# LED_7_Seg.net
KiCad netlist of a schematic drawn in Altium Designer
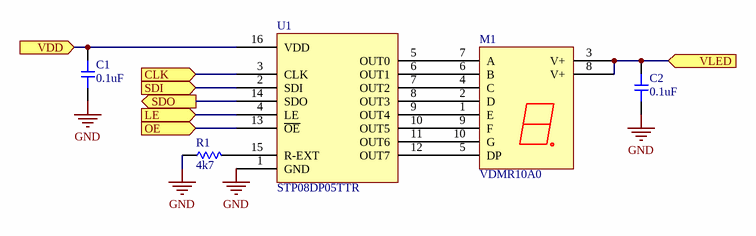
[diagram p0: LED_7_Seg.SchDoc]

(export (version "E")
  (design (tool "Eeschema 10.0.6"))
  (components
    (comp (ref "C1")
      (value "0.1uF")
      (footprint "PcbLib:0603-CAP")
      (description "Capacitor")
      (libsource (lib "AMDC") (part "Capacitor"))
    )
    (comp (ref "C2")
      (value "0.1uF")
      (footprint "PcbLib:0603-CAP")
      (description "Capacitor")
      (libsource (lib "AMDC") (part "Capacitor"))
    )
    (comp (ref "M1")
      (value "VDMR10A0")
      (footprint "VDMR10A0")
      (description "DISPLAY 7SEG 0.39\" SGL RED 10SMD")
      (libsource (lib "Schlib") (part "VDMR10A0"))
    )
    (comp (ref "R1")
      (value "4k7")
      (footprint "PcbLib:0603-RES")
      (fields (field (name "Comment") "Resistor"))
      (libsource (lib "*") (part "Resistor"))
    )
    (comp (ref "U1")
      (value "STP08DP05TTR")
      (footprint "TSOP65P640X120-16N")
      (description "IC LED DRIVER LIN 100MA 16TSSOP")
      (libsource (lib "Schlib") (part "STP08DP05TTR"))
    )
  )
  (nets
    (net (code "1") (name "/CLK") (class "Default")
      (node (ref "U1") (pin "3") (pinfunction "CLK_3") (pintype "passive"))
    )
    (net (code "2") (name "/LE") (class "Default")
      (node (ref "U1") (pin "4") (pinfunction "LE_4") (pintype "passive"))
    )
    (net (code "3") (name "/OE") (class "Default")
      (node (ref "U1") (pin "13") (pinfunction "~{OE}_13") (pintype "passive"))
    )
    (net (code "4") (name "/SDI") (class "Default")
      (node (ref "U1") (pin "2") (pinfunction "SDI_2") (pintype "passive"))
    )
    (net (code "5") (name "/SDO") (class "Default")
      (node (ref "U1") (pin "14") (pinfunction "SDO_14") (pintype "passive"))
    )
    (net (code "6") (name "/VDD") (class "Default")
      (node (ref "C1") (pin "1") (pinfunction "1_1") (pintype "passive"))
      (node (ref "U1") (pin "16") (pinfunction "VDD_16") (pintype "passive"))
    )
    (net (code "7") (name "/VLED") (class "Default")
      (node (ref "C2") (pin "1") (pinfunction "1_1") (pintype "passive"))
      (node (ref "M1") (pin "3") (pinfunction "V+_3") (pintype "passive"))
      (node (ref "M1") (pin "8") (pinfunction "V+_8") (pintype "passive"))
    )
    (net (code "8") (name "GND") (class "Default")
      (node (ref "C1") (pin "2") (pinfunction "2_2") (pintype "passive"))
      (node (ref "C2") (pin "2") (pinfunction "2_2") (pintype "passive"))
      (node (ref "R1") (pin "1") (pinfunction "1_1") (pintype "passive"))
      (node (ref "U1") (pin "1") (pinfunction "GND_1") (pintype "passive"))
    )
    (net (code "9") (name "Net-(M1-A)") (class "Default")
      (node (ref "M1") (pin "7") (pinfunction "A_7") (pintype "passive"))
      (node (ref "U1") (pin "5") (pinfunction "OUT0_5") (pintype "passive"))
    )
    (net (code "10") (name "Net-(M1-B)") (class "Default")
      (node (ref "M1") (pin "6") (pinfunction "B_6") (pintype "passive"))
      (node (ref "U1") (pin "6") (pinfunction "OUT1_6") (pintype "passive"))
    )
    (net (code "11") (name "Net-(M1-C)") (class "Default")
      (node (ref "M1") (pin "4") (pinfunction "C_4") (pintype "passive"))
      (node (ref "U1") (pin "7") (pinfunction "OUT2_7") (pintype "passive"))
    )
    (net (code "12") (name "Net-(M1-D)") (class "Default")
      (node (ref "M1") (pin "2") (pinfunction "D_2") (pintype "passive"))
      (node (ref "U1") (pin "8") (pinfunction "OUT3_8") (pintype "passive"))
    )
    (net (code "13") (name "Net-(M1-DP)") (class "Default")
      (node (ref "M1") (pin "5") (pinfunction "DP_5") (pintype "passive"))
      (node (ref "U1") (pin "12") (pinfunction "OUT7_12") (pintype "passive"))
    )
    (net (code "14") (name "Net-(M1-E)") (class "Default")
      (node (ref "M1") (pin "1") (pinfunction "E_1") (pintype "passive"))
      (node (ref "U1") (pin "9") (pinfunction "OUT4_9") (pintype "passive"))
    )
    (net (code "15") (name "Net-(M1-F)") (class "Default")
      (node (ref "M1") (pin "9") (pinfunction "F_9") (pintype "passive"))
      (node (ref "U1") (pin "10") (pinfunction "OUT5_10") (pintype "passive"))
    )
    (net (code "16") (name "Net-(M1-G)") (class "Default")
      (node (ref "M1") (pin "10") (pinfunction "G_10") (pintype "passive"))
      (node (ref "U1") (pin "11") (pinfunction "OUT6_11") (pintype "passive"))
    )
    (net (code "17") (name "Net-(U1-R-EXT)") (class "Default")
      (node (ref "R1") (pin "2") (pinfunction "2_2") (pintype "passive"))
      (node (ref "U1") (pin "15") (pinfunction "R-EXT_15") (pintype "passive"))
    )
  )
)
